# leds.net
KiCad netlist of a schematic drawn in Altium Designer
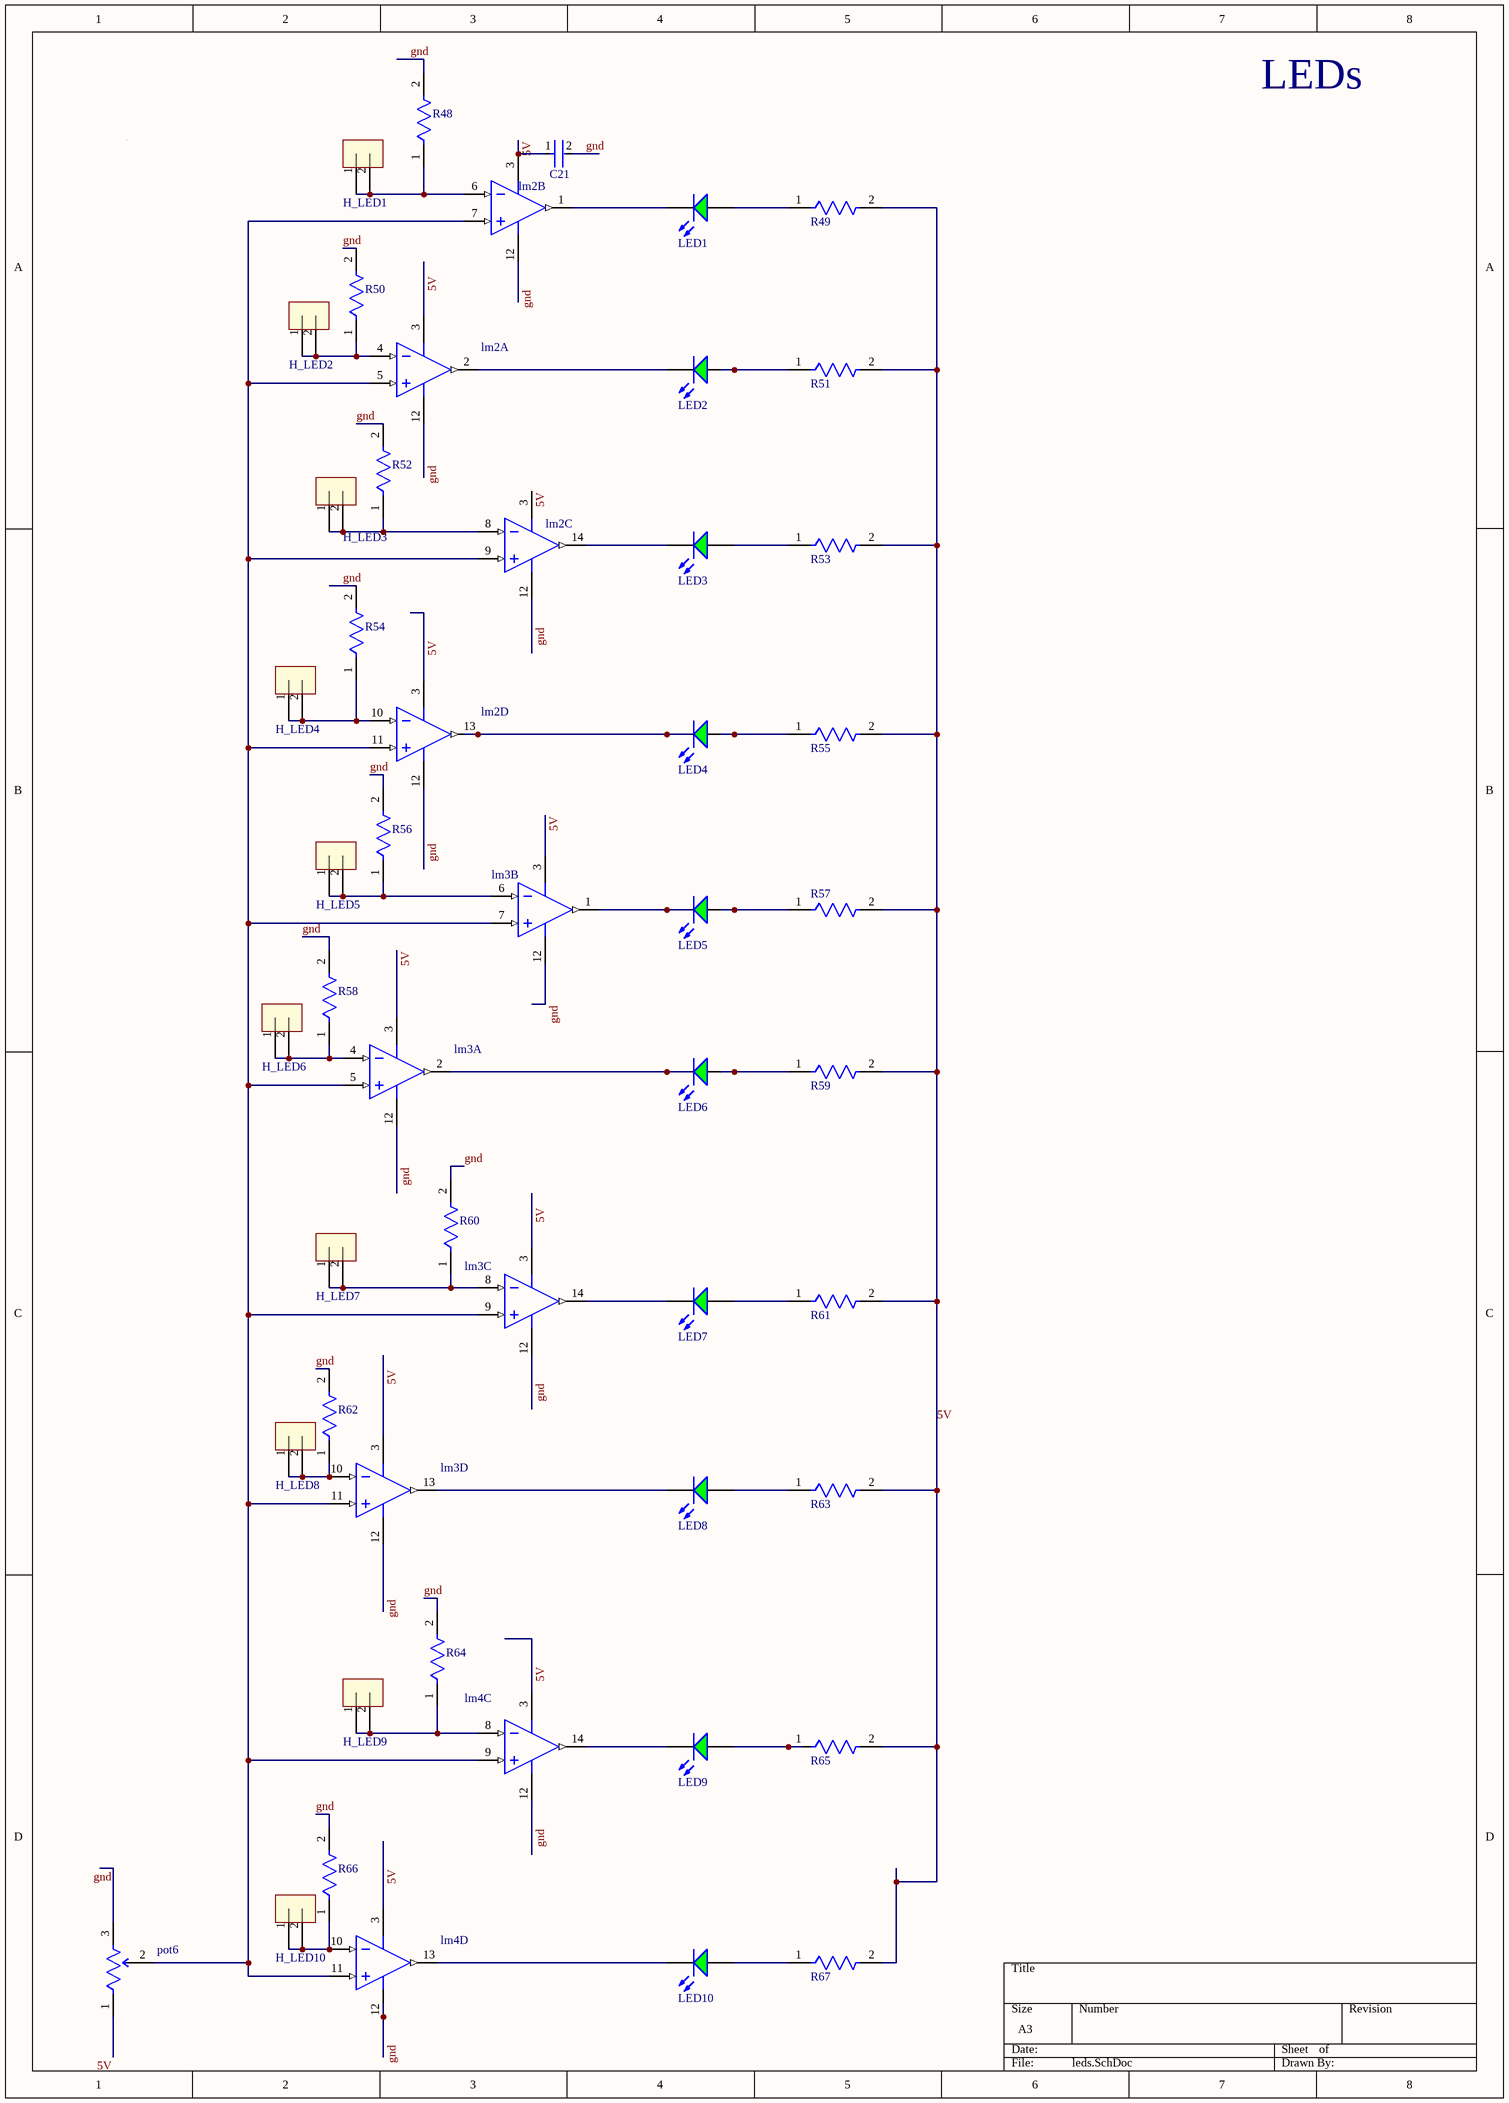
[diagram p0: leds.SchDoc]

(export (version "E")
  (design (tool "Eeschema 10.0.6"))
  (components
    (comp (ref "C21")
      (value "RCER71H335K3K1H03B")
      (footprint "FP-RCE3M1-MFG")
      (description "Cap Ceramic 3.3uF 50V X7R ±10% Radial 5mm +125°C Automotive Ammo Pack")
      (fields (field (name "TOLERANCE") "10%"))
      (libsource (lib "Altium Content Vault") (part "02cd4be3c70576c341d710602a673aa"))
    )
    (comp (ref "H_LED1")
      (value "header 2x1")
      (footprint "header 2x1")
      (description "header male 2 pin")
      (libsource (lib "Schlib1") (part "Heade 1x2"))
    )
    (comp (ref "H_LED2")
      (value "header 2x1")
      (footprint "header 2x1")
      (description "header male 2 pin")
      (libsource (lib "Schlib1") (part "Heade 1x2"))
    )
    (comp (ref "H_LED3")
      (value "header 2x1")
      (footprint "header 2x1")
      (description "header male 2 pin")
      (libsource (lib "Schlib1") (part "Heade 1x2"))
    )
    (comp (ref "H_LED4")
      (value "header 2x1")
      (footprint "header 2x1")
      (description "header male 2 pin")
      (libsource (lib "Schlib1") (part "Heade 1x2"))
    )
    (comp (ref "H_LED5")
      (value "header 2x1")
      (footprint "header 2x1")
      (description "header male 2 pin")
      (libsource (lib "Schlib1") (part "Heade 1x2"))
    )
    (comp (ref "H_LED6")
      (value "header 2x1")
      (footprint "header 2x1")
      (description "header male 2 pin")
      (libsource (lib "Schlib1") (part "Heade 1x2"))
    )
    (comp (ref "H_LED7")
      (value "header 2x1")
      (footprint "header 2x1")
      (description "header male 2 pin")
      (libsource (lib "Schlib1") (part "Heade 1x2"))
    )
    (comp (ref "H_LED8")
      (value "header 2x1")
      (footprint "header 2x1")
      (description "header male 2 pin")
      (libsource (lib "Schlib1") (part "Heade 1x2"))
    )
    (comp (ref "H_LED9")
      (value "header 2x1")
      (footprint "header 2x1")
      (description "header male 2 pin")
      (libsource (lib "Schlib1") (part "Heade 1x2"))
    )
    (comp (ref "H_LED10")
      (value "header 2x1")
      (footprint "header 2x1")
      (description "header male 2 pin")
      (libsource (lib "Schlib1") (part "Heade 1x2"))
    )
    (comp (ref "LED1")
      (value "WP7113SGD")
      (footprint "KING-WP7113SGD_V")
      (description "LED Green, 62.5 mW, 25 mA, -40 to 85 degC, 2-Pin THD, RoHS, Bulk")
      (fields (field (name "MANUFACTURER") "Kingbright"))
      (libsource (lib "Altium Content Vault") (part "LED-GREEN-AK-2"))
    )
    (comp (ref "LED2")
      (value "WP7113SGD")
      (footprint "KING-WP7113SGD_V")
      (description "LED Green, 62.5 mW, 25 mA, -40 to 85 degC, 2-Pin THD, RoHS, Bulk")
      (fields (field (name "MANUFACTURER") "Kingbright"))
      (libsource (lib "Altium Content Vault") (part "LED-GREEN-AK-2"))
    )
    (comp (ref "LED3")
      (value "WP7113SGD")
      (footprint "KING-WP7113SGD_V")
      (description "LED Green, 62.5 mW, 25 mA, -40 to 85 degC, 2-Pin THD, RoHS, Bulk")
      (fields (field (name "MANUFACTURER") "Kingbright"))
      (libsource (lib "Altium Content Vault") (part "LED-GREEN-AK-2"))
    )
    (comp (ref "LED4")
      (value "WP7113SGD")
      (footprint "KING-WP7113SGD_V")
      (description "LED Green, 62.5 mW, 25 mA, -40 to 85 degC, 2-Pin THD, RoHS, Bulk")
      (fields (field (name "MANUFACTURER") "Kingbright"))
      (libsource (lib "Altium Content Vault") (part "LED-GREEN-AK-2"))
    )
    (comp (ref "LED5")
      (value "WP7113SGD")
      (footprint "KING-WP7113SGD_V")
      (description "LED Green, 62.5 mW, 25 mA, -40 to 85 degC, 2-Pin THD, RoHS, Bulk")
      (fields (field (name "MANUFACTURER") "Kingbright"))
      (libsource (lib "Altium Content Vault") (part "LED-GREEN-AK-2"))
    )
    (comp (ref "LED6")
      (value "WP7113SGD")
      (footprint "KING-WP7113SGD_V")
      (description "LED Green, 62.5 mW, 25 mA, -40 to 85 degC, 2-Pin THD, RoHS, Bulk")
      (fields (field (name "MANUFACTURER") "Kingbright"))
      (libsource (lib "Altium Content Vault") (part "LED-GREEN-AK-2"))
    )
    (comp (ref "LED7")
      (value "WP7113SGD")
      (footprint "KING-WP7113SGD_V")
      (description "LED Green, 62.5 mW, 25 mA, -40 to 85 degC, 2-Pin THD, RoHS, Bulk")
      (fields (field (name "MANUFACTURER") "Kingbright"))
      (libsource (lib "Altium Content Vault") (part "LED-GREEN-AK-2"))
    )
    (comp (ref "LED8")
      (value "WP7113SGD")
      (footprint "KING-WP7113SGD_V")
      (description "LED Green, 62.5 mW, 25 mA, -40 to 85 degC, 2-Pin THD, RoHS, Bulk")
      (fields (field (name "MANUFACTURER") "Kingbright"))
      (libsource (lib "Altium Content Vault") (part "LED-GREEN-AK-2"))
    )
    (comp (ref "LED9")
      (value "WP7113SGD")
      (footprint "KING-WP7113SGD_V")
      (description "LED Green, 62.5 mW, 25 mA, -40 to 85 degC, 2-Pin THD, RoHS, Bulk")
      (fields (field (name "MANUFACTURER") "Kingbright"))
      (libsource (lib "Altium Content Vault") (part "LED-GREEN-AK-2"))
    )
    (comp (ref "LED10")
      (value "WP7113SGD")
      (footprint "KING-WP7113SGD_V")
      (description "LED Green, 62.5 mW, 25 mA, -40 to 85 degC, 2-Pin THD, RoHS, Bulk")
      (fields (field (name "MANUFACTURER") "Kingbright"))
      (libsource (lib "Altium Content Vault") (part "LED-GREEN-AK-2"))
    )
    (comp (ref "lm2")
      (value "LM339J")
      (footprint "J0014A")
      (description "Low Power Low Offset Voltage Quad Comparator, 14-pin CerDIP")
      (fields (field (name "MANUFACTURER") "Texas Instruments"))
      (libsource (lib "Altium Content Vault") (part "AN-COMP-LM139-14"))
    )
    (comp (ref "lm3")
      (value "LM339J")
      (footprint "J0014A")
      (description "Low Power Low Offset Voltage Quad Comparator, 14-pin CerDIP")
      (fields (field (name "MANUFACTURER") "Texas Instruments"))
      (libsource (lib "Altium Content Vault") (part "AN-COMP-LM139-14"))
    )
    (comp (ref "lm4")
      (value "LM339J")
      (footprint "J0014A")
      (description "Low Power Low Offset Voltage Quad Comparator, 14-pin CerDIP")
      (fields (field (name "MANUFACTURER") "Texas Instruments"))
      (libsource (lib "Altium Content Vault") (part "AN-COMP-LM139-14"))
    )
    (comp (ref "pot6")
      (value "3296W-1-501LF")
      (footprint "FP-3296W-MFG")
      (description "TRIMMER 500 OHM 0.5W PC PIN TOP")
      (fields (field (name "TOLERANCE") "10%"))
      (libsource (lib "Altium Content Vault") (part "2dcfd2547301a7d3209a5e99acfd772"))
    )
    (comp (ref "R48")
      (value "MRS16000C2002FCT00")
      (footprint "FP-MRS1600-MFG")
      (description "RES 20K OHM 0.4W 1% AXIAL")
      (fields (field (name "TOLERANCE") "1%"))
      (libsource (lib "Altium Content Vault") (part "1029c3af85768c4190bb7ad29bc67b5"))
    )
    (comp (ref "R49")
      (value "MRS16000C2002FCT00")
      (footprint "FP-MRS1600-MFG")
      (description "RES 20K OHM 0.4W 1% AXIAL")
      (fields (field (name "TOLERANCE") "1%"))
      (libsource (lib "Altium Content Vault") (part "1029c3af85768c4190bb7ad29bc67b5"))
    )
    (comp (ref "R50")
      (value "MRS16000C2002FCT00")
      (footprint "FP-MRS1600-MFG")
      (description "RES 20K OHM 0.4W 1% AXIAL")
      (fields (field (name "TOLERANCE") "1%"))
      (libsource (lib "Altium Content Vault") (part "1029c3af85768c4190bb7ad29bc67b5"))
    )
    (comp (ref "R51")
      (value "MRS16000C2002FCT00")
      (footprint "FP-MRS1600-MFG")
      (description "RES 20K OHM 0.4W 1% AXIAL")
      (fields (field (name "TOLERANCE") "1%"))
      (libsource (lib "Altium Content Vault") (part "1029c3af85768c4190bb7ad29bc67b5"))
    )
    (comp (ref "R52")
      (value "MRS16000C2002FCT00")
      (footprint "FP-MRS1600-MFG")
      (description "RES 20K OHM 0.4W 1% AXIAL")
      (fields (field (name "TOLERANCE") "1%"))
      (libsource (lib "Altium Content Vault") (part "1029c3af85768c4190bb7ad29bc67b5"))
    )
    (comp (ref "R53")
      (value "MRS16000C2002FCT00")
      (footprint "FP-MRS1600-MFG")
      (description "RES 20K OHM 0.4W 1% AXIAL")
      (fields (field (name "TOLERANCE") "1%"))
      (libsource (lib "Altium Content Vault") (part "1029c3af85768c4190bb7ad29bc67b5"))
    )
    (comp (ref "R54")
      (value "MRS16000C2002FCT00")
      (footprint "FP-MRS1600-MFG")
      (description "RES 20K OHM 0.4W 1% AXIAL")
      (fields (field (name "TOLERANCE") "1%"))
      (libsource (lib "Altium Content Vault") (part "1029c3af85768c4190bb7ad29bc67b5"))
    )
    (comp (ref "R55")
      (value "MRS16000C2002FCT00")
      (footprint "FP-MRS1600-MFG")
      (description "RES 20K OHM 0.4W 1% AXIAL")
      (fields (field (name "TOLERANCE") "1%"))
      (libsource (lib "Altium Content Vault") (part "1029c3af85768c4190bb7ad29bc67b5"))
    )
    (comp (ref "R56")
      (value "MRS16000C2002FCT00")
      (footprint "FP-MRS1600-MFG")
      (description "RES 20K OHM 0.4W 1% AXIAL")
      (fields (field (name "TOLERANCE") "1%"))
      (libsource (lib "Altium Content Vault") (part "1029c3af85768c4190bb7ad29bc67b5"))
    )
    (comp (ref "R57")
      (value "MRS16000C2002FCT00")
      (footprint "FP-MRS1600-MFG")
      (description "RES 20K OHM 0.4W 1% AXIAL")
      (fields (field (name "TOLERANCE") "1%"))
      (libsource (lib "Altium Content Vault") (part "1029c3af85768c4190bb7ad29bc67b5"))
    )
    (comp (ref "R58")
      (value "MRS16000C2002FCT00")
      (footprint "FP-MRS1600-MFG")
      (description "RES 20K OHM 0.4W 1% AXIAL")
      (fields (field (name "TOLERANCE") "1%"))
      (libsource (lib "Altium Content Vault") (part "1029c3af85768c4190bb7ad29bc67b5"))
    )
    (comp (ref "R59")
      (value "MRS16000C2002FCT00")
      (footprint "FP-MRS1600-MFG")
      (description "RES 20K OHM 0.4W 1% AXIAL")
      (fields (field (name "TOLERANCE") "1%"))
      (libsource (lib "Altium Content Vault") (part "1029c3af85768c4190bb7ad29bc67b5"))
    )
    (comp (ref "R60")
      (value "MRS16000C2002FCT00")
      (footprint "FP-MRS1600-MFG")
      (description "RES 20K OHM 0.4W 1% AXIAL")
      (fields (field (name "TOLERANCE") "1%"))
      (libsource (lib "Altium Content Vault") (part "1029c3af85768c4190bb7ad29bc67b5"))
    )
    (comp (ref "R61")
      (value "MRS16000C2002FCT00")
      (footprint "FP-MRS1600-MFG")
      (description "RES 20K OHM 0.4W 1% AXIAL")
      (fields (field (name "TOLERANCE") "1%"))
      (libsource (lib "Altium Content Vault") (part "1029c3af85768c4190bb7ad29bc67b5"))
    )
    (comp (ref "R62")
      (value "MRS16000C2002FCT00")
      (footprint "FP-MRS1600-MFG")
      (description "RES 20K OHM 0.4W 1% AXIAL")
      (fields (field (name "TOLERANCE") "1%"))
      (libsource (lib "Altium Content Vault") (part "1029c3af85768c4190bb7ad29bc67b5"))
    )
    (comp (ref "R63")
      (value "MRS16000C2002FCT00")
      (footprint "FP-MRS1600-MFG")
      (description "RES 20K OHM 0.4W 1% AXIAL")
      (fields (field (name "TOLERANCE") "1%"))
      (libsource (lib "Altium Content Vault") (part "1029c3af85768c4190bb7ad29bc67b5"))
    )
    (comp (ref "R64")
      (value "MRS16000C2002FCT00")
      (footprint "FP-MRS1600-MFG")
      (description "RES 20K OHM 0.4W 1% AXIAL")
      (fields (field (name "TOLERANCE") "1%"))
      (libsource (lib "Altium Content Vault") (part "1029c3af85768c4190bb7ad29bc67b5"))
    )
    (comp (ref "R65")
      (value "MRS16000C2002FCT00")
      (footprint "FP-MRS1600-MFG")
      (description "RES 20K OHM 0.4W 1% AXIAL")
      (fields (field (name "TOLERANCE") "1%"))
      (libsource (lib "Altium Content Vault") (part "1029c3af85768c4190bb7ad29bc67b5"))
    )
    (comp (ref "R66")
      (value "MRS16000C2002FCT00")
      (footprint "FP-MRS1600-MFG")
      (description "RES 20K OHM 0.4W 1% AXIAL")
      (fields (field (name "TOLERANCE") "1%"))
      (libsource (lib "Altium Content Vault") (part "1029c3af85768c4190bb7ad29bc67b5"))
    )
    (comp (ref "R67")
      (value "MRS16000C2002FCT00")
      (footprint "FP-MRS1600-MFG")
      (description "RES 20K OHM 0.4W 1% AXIAL")
      (fields (field (name "TOLERANCE") "1%"))
      (libsource (lib "Altium Content Vault") (part "1029c3af85768c4190bb7ad29bc67b5"))
    )
  )
  (nets
    (net (code "1") (name "/5V") (class "Default")
      (node (ref "C21") (pin "1") (pinfunction "1_1") (pintype "passive"))
      (node (ref "R49") (pin "2") (pinfunction "2_2") (pintype "passive"))
      (node (ref "R51") (pin "2") (pinfunction "2_2") (pintype "passive"))
      (node (ref "R53") (pin "2") (pinfunction "2_2") (pintype "passive"))
      (node (ref "R55") (pin "2") (pinfunction "2_2") (pintype "passive"))
      (node (ref "R57") (pin "2") (pinfunction "2_2") (pintype "passive"))
      (node (ref "R59") (pin "2") (pinfunction "2_2") (pintype "passive"))
      (node (ref "R61") (pin "2") (pinfunction "2_2") (pintype "passive"))
      (node (ref "R63") (pin "2") (pinfunction "2_2") (pintype "passive"))
      (node (ref "R65") (pin "2") (pinfunction "2_2") (pintype "passive"))
      (node (ref "R67") (pin "2") (pinfunction "2_2") (pintype "passive"))
      (node (ref "lm2") (pin "3") (pinfunction "V+_3") (pintype "power_in"))
      (node (ref "lm3") (pin "3") (pinfunction "V+_3") (pintype "power_in"))
      (node (ref "lm4") (pin "3") (pinfunction "V+_3") (pintype "power_in"))
      (node (ref "pot6") (pin "1") (pinfunction "CCW_1") (pintype "passive"))
    )
    (net (code "2") (name "/gnd") (class "Default")
      (node (ref "C21") (pin "2") (pinfunction "2_2") (pintype "passive"))
      (node (ref "R48") (pin "2") (pinfunction "2_2") (pintype "passive"))
      (node (ref "R50") (pin "2") (pinfunction "2_2") (pintype "passive"))
      (node (ref "R52") (pin "2") (pinfunction "2_2") (pintype "passive"))
      (node (ref "R54") (pin "2") (pinfunction "2_2") (pintype "passive"))
      (node (ref "R56") (pin "2") (pinfunction "2_2") (pintype "passive"))
      (node (ref "R58") (pin "2") (pinfunction "2_2") (pintype "passive"))
      (node (ref "R60") (pin "2") (pinfunction "2_2") (pintype "passive"))
      (node (ref "R62") (pin "2") (pinfunction "2_2") (pintype "passive"))
      (node (ref "R64") (pin "2") (pinfunction "2_2") (pintype "passive"))
      (node (ref "R66") (pin "2") (pinfunction "2_2") (pintype "passive"))
      (node (ref "lm2") (pin "12") (pinfunction "GND_12") (pintype "power_in"))
      (node (ref "lm3") (pin "12") (pinfunction "GND_12") (pintype "power_in"))
      (node (ref "lm4") (pin "12") (pinfunction "GND_12") (pintype "power_in"))
      (node (ref "pot6") (pin "3") (pinfunction "CW_3") (pintype "passive"))
    )
    (net (code "3") (name "Net-(LED1-A)") (class "Default")
      (node (ref "LED1") (pin "1") (pinfunction "A_1") (pintype "passive"))
      (node (ref "R49") (pin "1") (pinfunction "1_1") (pintype "passive"))
    )
    (net (code "4") (name "Net-(LED1-K)") (class "Default")
      (node (ref "LED1") (pin "2") (pinfunction "K_2") (pintype "passive"))
      (node (ref "lm2") (pin "1") (pinfunction "OUT2_1") (pintype "output"))
    )
    (net (code "5") (name "Net-(LED2-A)") (class "Default")
      (node (ref "LED2") (pin "1") (pinfunction "A_1") (pintype "passive"))
      (node (ref "R51") (pin "1") (pinfunction "1_1") (pintype "passive"))
    )
    (net (code "6") (name "Net-(LED2-K)") (class "Default")
      (node (ref "LED2") (pin "2") (pinfunction "K_2") (pintype "passive"))
      (node (ref "lm2") (pin "2") (pinfunction "OUT1_2") (pintype "output"))
    )
    (net (code "7") (name "Net-(LED3-A)") (class "Default")
      (node (ref "LED3") (pin "1") (pinfunction "A_1") (pintype "passive"))
      (node (ref "R53") (pin "1") (pinfunction "1_1") (pintype "passive"))
    )
    (net (code "8") (name "Net-(LED3-K)") (class "Default")
      (node (ref "LED3") (pin "2") (pinfunction "K_2") (pintype "passive"))
      (node (ref "lm2") (pin "14") (pinfunction "OUT3_14") (pintype "output"))
    )
    (net (code "9") (name "Net-(LED4-A)") (class "Default")
      (node (ref "LED4") (pin "1") (pinfunction "A_1") (pintype "passive"))
      (node (ref "R55") (pin "1") (pinfunction "1_1") (pintype "passive"))
    )
    (net (code "10") (name "Net-(LED4-K)") (class "Default")
      (node (ref "LED4") (pin "2") (pinfunction "K_2") (pintype "passive"))
      (node (ref "lm2") (pin "13") (pinfunction "OUT4_13") (pintype "output"))
    )
    (net (code "11") (name "Net-(LED5-A)") (class "Default")
      (node (ref "LED5") (pin "1") (pinfunction "A_1") (pintype "passive"))
      (node (ref "R57") (pin "1") (pinfunction "1_1") (pintype "passive"))
    )
    (net (code "12") (name "Net-(LED5-K)") (class "Default")
      (node (ref "LED5") (pin "2") (pinfunction "K_2") (pintype "passive"))
      (node (ref "lm3") (pin "1") (pinfunction "OUT2_1") (pintype "output"))
    )
    (net (code "13") (name "Net-(LED6-A)") (class "Default")
      (node (ref "LED6") (pin "1") (pinfunction "A_1") (pintype "passive"))
      (node (ref "R59") (pin "1") (pinfunction "1_1") (pintype "passive"))
    )
    (net (code "14") (name "Net-(LED6-K)") (class "Default")
      (node (ref "LED6") (pin "2") (pinfunction "K_2") (pintype "passive"))
      (node (ref "lm3") (pin "2") (pinfunction "OUT1_2") (pintype "output"))
    )
    (net (code "15") (name "Net-(LED7-A)") (class "Default")
      (node (ref "LED7") (pin "1") (pinfunction "A_1") (pintype "passive"))
      (node (ref "R61") (pin "1") (pinfunction "1_1") (pintype "passive"))
    )
    (net (code "16") (name "Net-(LED7-K)") (class "Default")
      (node (ref "LED7") (pin "2") (pinfunction "K_2") (pintype "passive"))
      (node (ref "lm3") (pin "14") (pinfunction "OUT3_14") (pintype "output"))
    )
    (net (code "17") (name "Net-(LED8-A)") (class "Default")
      (node (ref "LED8") (pin "1") (pinfunction "A_1") (pintype "passive"))
      (node (ref "R63") (pin "1") (pinfunction "1_1") (pintype "passive"))
    )
    (net (code "18") (name "Net-(LED8-K)") (class "Default")
      (node (ref "LED8") (pin "2") (pinfunction "K_2") (pintype "passive"))
      (node (ref "lm3") (pin "13") (pinfunction "OUT4_13") (pintype "output"))
    )
    (net (code "19") (name "Net-(LED9-A)") (class "Default")
      (node (ref "LED9") (pin "1") (pinfunction "A_1") (pintype "passive"))
      (node (ref "R65") (pin "1") (pinfunction "1_1") (pintype "passive"))
    )
    (net (code "20") (name "Net-(LED9-K)") (class "Default")
      (node (ref "LED9") (pin "2") (pinfunction "K_2") (pintype "passive"))
      (node (ref "lm4") (pin "14") (pinfunction "OUT3_14") (pintype "output"))
    )
    (net (code "21") (name "Net-(LED10-A)") (class "Default")
      (node (ref "LED10") (pin "1") (pinfunction "A_1") (pintype "passive"))
      (node (ref "R67") (pin "1") (pinfunction "1_1") (pintype "passive"))
    )
    (net (code "22") (name "Net-(LED10-K)") (class "Default")
      (node (ref "LED10") (pin "2") (pinfunction "K_2") (pintype "passive"))
      (node (ref "lm4") (pin "13") (pinfunction "OUT4_13") (pintype "output"))
    )
    (net (code "23") (name "Net-(lm2A-IN1+)") (class "Default")
      (node (ref "lm2") (pin "11") (pinfunction "IN4+_11") (pintype "input"))
      (node (ref "lm2") (pin "5") (pinfunction "IN1+_5") (pintype "input"))
      (node (ref "lm2") (pin "7") (pinfunction "IN2+_7") (pintype "input"))
      (node (ref "lm2") (pin "9") (pinfunction "IN3+_9") (pintype "input"))
      (node (ref "lm3") (pin "11") (pinfunction "IN4+_11") (pintype "input"))
      (node (ref "lm3") (pin "5") (pinfunction "IN1+_5") (pintype "input"))
      (node (ref "lm3") (pin "7") (pinfunction "IN2+_7") (pintype "input"))
      (node (ref "lm3") (pin "9") (pinfunction "IN3+_9") (pintype "input"))
      (node (ref "lm4") (pin "11") (pinfunction "IN4+_11") (pintype "input"))
      (node (ref "lm4") (pin "9") (pinfunction "IN3+_9") (pintype "input"))
      (node (ref "pot6") (pin "2") (pinfunction "WIPER_2") (pintype "passive"))
    )
    (net (code "24") (name "Net-(lm2A-IN1-)") (class "Default")
      (node (ref "H_LED2") (pin "1") (pinfunction "1_1") (pintype "passive"))
      (node (ref "H_LED2") (pin "2") (pinfunction "2_2") (pintype "passive"))
      (node (ref "R50") (pin "1") (pinfunction "1_1") (pintype "passive"))
      (node (ref "lm2") (pin "4") (pinfunction "IN1-_4") (pintype "input"))
    )
    (net (code "25") (name "Net-(lm2B-IN2-)") (class "Default")
      (node (ref "H_LED1") (pin "1") (pinfunction "1_1") (pintype "passive"))
      (node (ref "H_LED1") (pin "2") (pinfunction "2_2") (pintype "passive"))
      (node (ref "R48") (pin "1") (pinfunction "1_1") (pintype "passive"))
      (node (ref "lm2") (pin "6") (pinfunction "IN2-_6") (pintype "input"))
    )
    (net (code "26") (name "Net-(lm2C-IN3-)") (class "Default")
      (node (ref "H_LED3") (pin "1") (pinfunction "1_1") (pintype "passive"))
      (node (ref "H_LED3") (pin "2") (pinfunction "2_2") (pintype "passive"))
      (node (ref "R52") (pin "1") (pinfunction "1_1") (pintype "passive"))
      (node (ref "lm2") (pin "8") (pinfunction "IN3-_8") (pintype "input"))
    )
    (net (code "27") (name "Net-(lm2D-IN4-)") (class "Default")
      (node (ref "H_LED4") (pin "1") (pinfunction "1_1") (pintype "passive"))
      (node (ref "H_LED4") (pin "2") (pinfunction "2_2") (pintype "passive"))
      (node (ref "R54") (pin "1") (pinfunction "1_1") (pintype "passive"))
      (node (ref "lm2") (pin "10") (pinfunction "IN4-_10") (pintype "input"))
    )
    (net (code "28") (name "Net-(lm3A-IN1-)") (class "Default")
      (node (ref "H_LED6") (pin "1") (pinfunction "1_1") (pintype "passive"))
      (node (ref "H_LED6") (pin "2") (pinfunction "2_2") (pintype "passive"))
      (node (ref "R58") (pin "1") (pinfunction "1_1") (pintype "passive"))
      (node (ref "lm3") (pin "4") (pinfunction "IN1-_4") (pintype "input"))
    )
    (net (code "29") (name "Net-(lm3B-IN2-)") (class "Default")
      (node (ref "H_LED5") (pin "1") (pinfunction "1_1") (pintype "passive"))
      (node (ref "H_LED5") (pin "2") (pinfunction "2_2") (pintype "passive"))
      (node (ref "R56") (pin "1") (pinfunction "1_1") (pintype "passive"))
      (node (ref "lm3") (pin "6") (pinfunction "IN2-_6") (pintype "input"))
    )
    (net (code "30") (name "Net-(lm3C-IN3-)") (class "Default")
      (node (ref "H_LED7") (pin "1") (pinfunction "1_1") (pintype "passive"))
      (node (ref "H_LED7") (pin "2") (pinfunction "2_2") (pintype "passive"))
      (node (ref "R60") (pin "1") (pinfunction "1_1") (pintype "passive"))
      (node (ref "lm3") (pin "8") (pinfunction "IN3-_8") (pintype "input"))
    )
    (net (code "31") (name "Net-(lm3D-IN4-)") (class "Default")
      (node (ref "H_LED8") (pin "1") (pinfunction "1_1") (pintype "passive"))
      (node (ref "H_LED8") (pin "2") (pinfunction "2_2") (pintype "passive"))
      (node (ref "R62") (pin "1") (pinfunction "1_1") (pintype "passive"))
      (node (ref "lm3") (pin "10") (pinfunction "IN4-_10") (pintype "input"))
    )
    (net (code "32") (name "Net-(lm4C-IN3-)") (class "Default")
      (node (ref "H_LED9") (pin "1") (pinfunction "1_1") (pintype "passive"))
      (node (ref "H_LED9") (pin "2") (pinfunction "2_2") (pintype "passive"))
      (node (ref "R64") (pin "1") (pinfunction "1_1") (pintype "passive"))
      (node (ref "lm4") (pin "8") (pinfunction "IN3-_8") (pintype "input"))
    )
    (net (code "33") (name "Net-(lm4D-IN4-)") (class "Default")
      (node (ref "H_LED10") (pin "1") (pinfunction "1_1") (pintype "passive"))
      (node (ref "H_LED10") (pin "2") (pinfunction "2_2") (pintype "passive"))
      (node (ref "R66") (pin "1") (pinfunction "1_1") (pintype "passive"))
      (node (ref "lm4") (pin "10") (pinfunction "IN4-_10") (pintype "input"))
    )
  )
)
